# BPF.net
KiCad netlist of a schematic drawn in Altium Designer
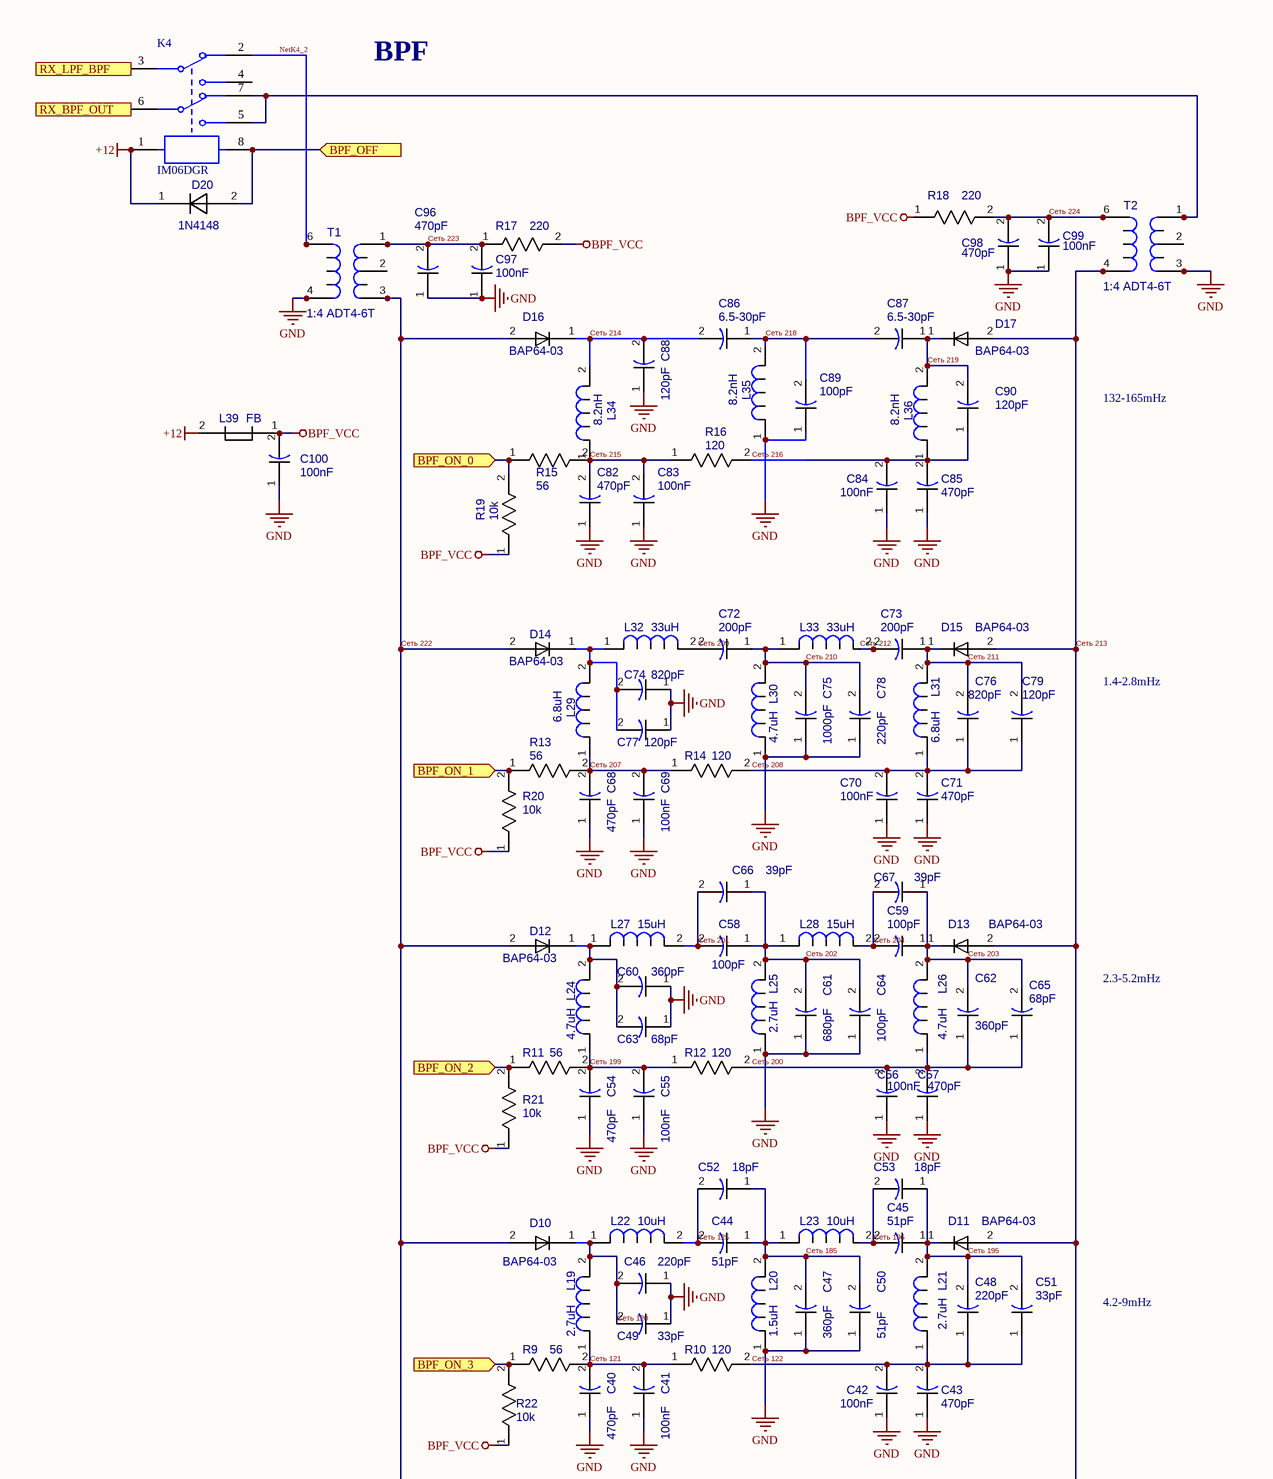
[diagram p0: BPF.SchDoc, top]
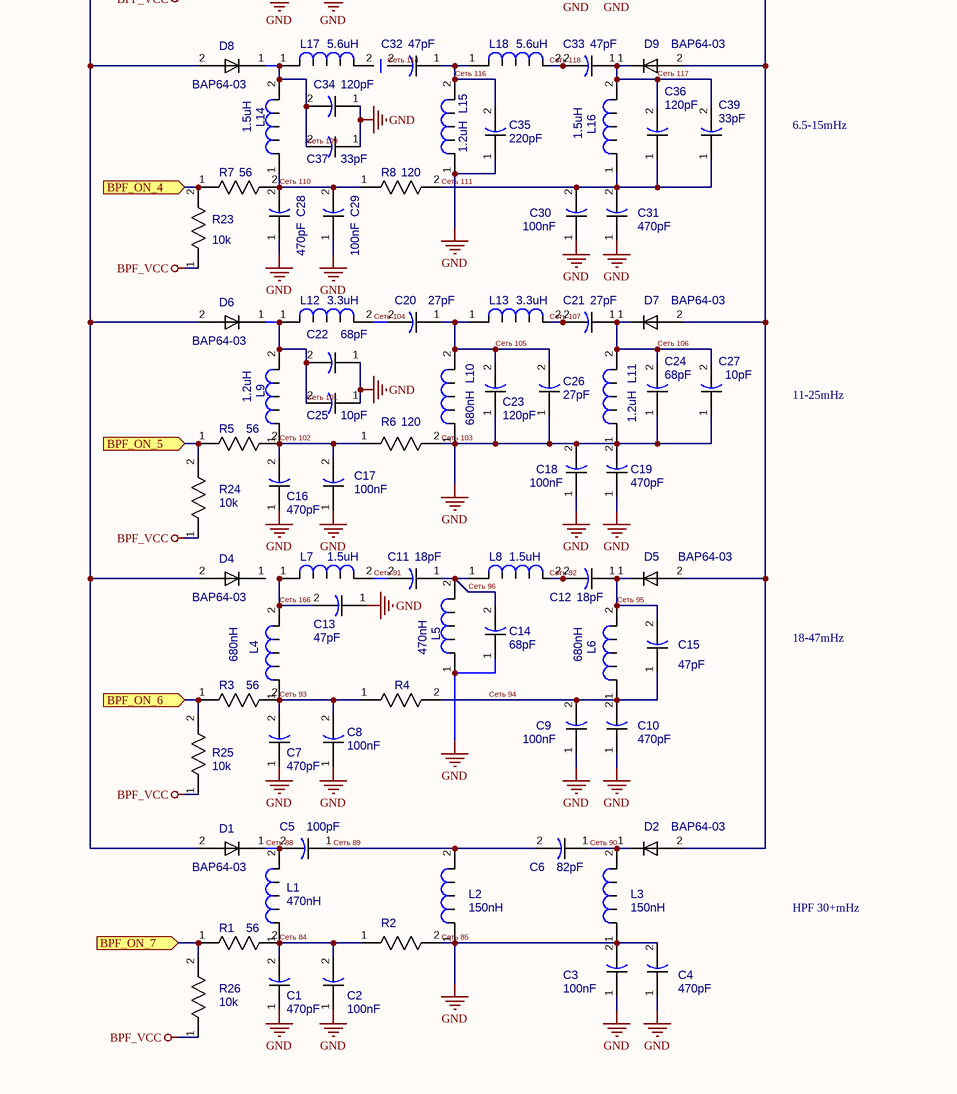
[diagram p1: BPF.SchDoc, bottom]

(export (version "E")
  (design (tool "Eeschema 10.0.6"))
  (components
    (comp (ref "C1")
      (value "470pF")
      (footprint "CAP_0805")
      (description "CAP_0805")
      (libsource (lib "*") (part "CAP_0805"))
    )
    (comp (ref "C2")
      (value "100nF")
      (footprint "CAP_0805")
      (description "CAP_0805")
      (libsource (lib "*") (part "CAP_0805"))
    )
    (comp (ref "C3")
      (value "100nF")
      (footprint "CAP_0805")
      (description "CAP_0805")
      (libsource (lib "*") (part "CAP_0805"))
    )
    (comp (ref "C4")
      (value "470pF")
      (footprint "CAP_0805")
      (description "CAP_0805")
      (libsource (lib "*") (part "CAP_0805"))
    )
    (comp (ref "C5")
      (value "100pF")
      (footprint "CAP_0805")
      (description "CAP_0805")
      (libsource (lib "*") (part "CAP_0805"))
    )
    (comp (ref "C6")
      (value "82pF")
      (footprint "CAP_0805")
      (description "CAP_0805")
      (libsource (lib "*") (part "CAP_0805"))
    )
    (comp (ref "C7")
      (value "470pF")
      (footprint "CAP_0805")
      (description "CAP_0805")
      (libsource (lib "*") (part "CAP_0805"))
    )
    (comp (ref "C8")
      (value "100nF")
      (footprint "CAP_0805")
      (description "CAP_0805")
      (libsource (lib "*") (part "CAP_0805"))
    )
    (comp (ref "C9")
      (value "100nF")
      (footprint "CAP_0805")
      (description "CAP_0805")
      (libsource (lib "*") (part "CAP_0805"))
    )
    (comp (ref "C10")
      (value "470pF")
      (footprint "CAP_0805")
      (description "CAP_0805")
      (libsource (lib "*") (part "CAP_0805"))
    )
    (comp (ref "C11")
      (value "18pF")
      (footprint "CAP_0805")
      (description "CAP_0805")
      (libsource (lib "*") (part "CAP_0805"))
    )
    (comp (ref "C12")
      (value "18pF")
      (footprint "CAP_0805")
      (description "CAP_0805")
      (libsource (lib "*") (part "CAP_0805"))
    )
    (comp (ref "C13")
      (value "47pF")
      (footprint "CAP_0805")
      (description "CAP_0805")
      (libsource (lib "*") (part "CAP_0805"))
    )
    (comp (ref "C14")
      (value "68pF")
      (footprint "CAP_0805")
      (description "CAP_0805")
      (libsource (lib "*") (part "CAP_0805"))
    )
    (comp (ref "C15")
      (value "47pF")
      (footprint "CAP_0805")
      (description "CAP_0805")
      (libsource (lib "*") (part "CAP_0805"))
    )
    (comp (ref "C16")
      (value "470pF")
      (footprint "CAP_0805")
      (description "CAP_0805")
      (libsource (lib "*") (part "CAP_0805"))
    )
    (comp (ref "C17")
      (value "100nF")
      (footprint "CAP_0805")
      (description "CAP_0805")
      (libsource (lib "*") (part "CAP_0805"))
    )
    (comp (ref "C18")
      (value "100nF")
      (footprint "CAP_0805")
      (description "CAP_0805")
      (libsource (lib "*") (part "CAP_0805"))
    )
    (comp (ref "C19")
      (value "470pF")
      (footprint "CAP_0805")
      (description "CAP_0805")
      (libsource (lib "*") (part "CAP_0805"))
    )
    (comp (ref "C20")
      (value "27pF")
      (footprint "CAP_0805")
      (description "CAP_0805")
      (libsource (lib "*") (part "CAP_0805"))
    )
    (comp (ref "C21")
      (value "27pF")
      (footprint "CAP_0805")
      (description "CAP_0805")
      (libsource (lib "*") (part "CAP_0805"))
    )
    (comp (ref "C22")
      (value "68pF")
      (footprint "CAP_0805")
      (description "CAP_0805")
      (libsource (lib "*") (part "CAP_0805"))
    )
    (comp (ref "C23")
      (value "120pF")
      (footprint "CAP_0805")
      (description "CAP_0805")
      (libsource (lib "*") (part "CAP_0805"))
    )
    (comp (ref "C24")
      (value "68pF")
      (footprint "CAP_0805")
      (description "CAP_0805")
      (libsource (lib "*") (part "CAP_0805"))
    )
    (comp (ref "C25")
      (value "10pF")
      (footprint "CAP_0805")
      (description "CAP_0805")
      (libsource (lib "*") (part "CAP_0805"))
    )
    (comp (ref "C26")
      (value "27pF")
      (footprint "CAP_0805")
      (description "CAP_0805")
      (libsource (lib "*") (part "CAP_0805"))
    )
    (comp (ref "C27")
      (value "10pF")
      (footprint "CAP_0805")
      (description "CAP_0805")
      (libsource (lib "*") (part "CAP_0805"))
    )
    (comp (ref "C28")
      (value "470pF")
      (footprint "CAP_0805")
      (description "CAP_0805")
      (libsource (lib "*") (part "CAP_0805"))
    )
    (comp (ref "C29")
      (value "100nF")
      (footprint "CAP_0805")
      (description "CAP_0805")
      (libsource (lib "*") (part "CAP_0805"))
    )
    (comp (ref "C30")
      (value "100nF")
      (footprint "CAP_0805")
      (description "CAP_0805")
      (libsource (lib "*") (part "CAP_0805"))
    )
    (comp (ref "C31")
      (value "470pF")
      (footprint "CAP_0805")
      (description "CAP_0805")
      (libsource (lib "*") (part "CAP_0805"))
    )
    (comp (ref "C32")
      (value "47pF")
      (footprint "CAP_0805")
      (description "CAP_0805")
      (libsource (lib "*") (part "CAP_0805"))
    )
    (comp (ref "C33")
      (value "47pF")
      (footprint "CAP_0805")
      (description "CAP_0805")
      (libsource (lib "*") (part "CAP_0805"))
    )
    (comp (ref "C34")
      (value "120pF")
      (footprint "CAP_0805")
      (description "CAP_0805")
      (libsource (lib "*") (part "CAP_0805"))
    )
    (comp (ref "C35")
      (value "220pF")
      (footprint "CAP_0805")
      (description "CAP_0805")
      (libsource (lib "*") (part "CAP_0805"))
    )
    (comp (ref "C36")
      (value "120pF")
      (footprint "CAP_0805")
      (description "CAP_0805")
      (libsource (lib "*") (part "CAP_0805"))
    )
    (comp (ref "C37")
      (value "33pF")
      (footprint "CAP_0805")
      (description "CAP_0805")
      (libsource (lib "*") (part "CAP_0805"))
    )
    (comp (ref "C39")
      (value "33pF")
      (footprint "CAP_0805")
      (description "CAP_0805")
      (libsource (lib "*") (part "CAP_0805"))
    )
    (comp (ref "C40")
      (value "470pF")
      (footprint "CAP_0805")
      (description "CAP_0805")
      (libsource (lib "*") (part "CAP_0805"))
    )
    (comp (ref "C41")
      (value "100nF")
      (footprint "CAP_0805")
      (description "CAP_0805")
      (libsource (lib "*") (part "CAP_0805"))
    )
    (comp (ref "C42")
      (value "100nF")
      (footprint "CAP_0805")
      (description "CAP_0805")
      (libsource (lib "*") (part "CAP_0805"))
    )
    (comp (ref "C43")
      (value "470pF")
      (footprint "CAP_0805")
      (description "CAP_0805")
      (libsource (lib "*") (part "CAP_0805"))
    )
    (comp (ref "C44")
      (value "51pF")
      (footprint "CAP_0805")
      (description "CAP_0805")
      (libsource (lib "*") (part "CAP_0805"))
    )
    (comp (ref "C45")
      (value "51pF")
      (footprint "CAP_0805")
      (description "CAP_0805")
      (libsource (lib "*") (part "CAP_0805"))
    )
    (comp (ref "C46")
      (value "220pF")
      (footprint "CAP_0805")
      (description "CAP_0805")
      (libsource (lib "*") (part "CAP_0805"))
    )
    (comp (ref "C47")
      (value "360pF")
      (footprint "CAP_0805")
      (description "CAP_0805")
      (libsource (lib "*") (part "CAP_0805"))
    )
    (comp (ref "C48")
      (value "220pF")
      (footprint "CAP_0805")
      (description "CAP_0805")
      (libsource (lib "*") (part "CAP_0805"))
    )
    (comp (ref "C49")
      (value "33pF")
      (footprint "CAP_0805")
      (description "CAP_0805")
      (libsource (lib "*") (part "CAP_0805"))
    )
    (comp (ref "C50")
      (value "51pF")
      (footprint "CAP_0805")
      (description "CAP_0805")
      (libsource (lib "*") (part "CAP_0805"))
    )
    (comp (ref "C51")
      (value "33pF")
      (footprint "CAP_0805")
      (description "CAP_0805")
      (libsource (lib "*") (part "CAP_0805"))
    )
    (comp (ref "C52")
      (value "18pF")
      (footprint "CAP_0805")
      (description "CAP_0805")
      (libsource (lib "*") (part "CAP_0805"))
    )
    (comp (ref "C53")
      (value "18pF")
      (footprint "CAP_0805")
      (description "CAP_0805")
      (libsource (lib "*") (part "CAP_0805"))
    )
    (comp (ref "C54")
      (value "470pF")
      (footprint "CAP_0805")
      (description "CAP_0805")
      (libsource (lib "*") (part "CAP_0805"))
    )
    (comp (ref "C55")
      (value "100nF")
      (footprint "CAP_0805")
      (description "CAP_0805")
      (libsource (lib "*") (part "CAP_0805"))
    )
    (comp (ref "C56")
      (value "100nF")
      (footprint "CAP_0805")
      (description "CAP_0805")
      (libsource (lib "*") (part "CAP_0805"))
    )
    (comp (ref "C57")
      (value "470pF")
      (footprint "CAP_0805")
      (description "CAP_0805")
      (libsource (lib "*") (part "CAP_0805"))
    )
    (comp (ref "C58")
      (value "100pF")
      (footprint "CAP_0805")
      (description "CAP_0805")
      (libsource (lib "*") (part "CAP_0805"))
    )
    (comp (ref "C59")
      (value "100pF")
      (footprint "CAP_0805")
      (description "CAP_0805")
      (libsource (lib "*") (part "CAP_0805"))
    )
    (comp (ref "C60")
      (value "360pF")
      (footprint "CAP_0805")
      (description "CAP_0805")
      (libsource (lib "*") (part "CAP_0805"))
    )
    (comp (ref "C61")
      (value "680pF")
      (footprint "CAP_0805")
      (description "CAP_0805")
      (libsource (lib "*") (part "CAP_0805"))
    )
    (comp (ref "C62")
      (value "360pF")
      (footprint "CAP_0805")
      (description "CAP_0805")
      (libsource (lib "*") (part "CAP_0805"))
    )
    (comp (ref "C63")
      (value "68pF")
      (footprint "CAP_0805")
      (description "CAP_0805")
      (libsource (lib "*") (part "CAP_0805"))
    )
    (comp (ref "C64")
      (value "100pF")
      (footprint "CAP_0805")
      (description "CAP_0805")
      (libsource (lib "*") (part "CAP_0805"))
    )
    (comp (ref "C65")
      (value "68pF")
      (footprint "CAP_0805")
      (description "CAP_0805")
      (libsource (lib "*") (part "CAP_0805"))
    )
    (comp (ref "C66")
      (value "39pF")
      (footprint "CAP_0805")
      (description "CAP_0805")
      (libsource (lib "*") (part "CAP_0805"))
    )
    (comp (ref "C67")
      (value "39pF")
      (footprint "CAP_0805")
      (description "CAP_0805")
      (libsource (lib "*") (part "CAP_0805"))
    )
    (comp (ref "C68")
      (value "470pF")
      (footprint "CAP_0805")
      (description "CAP_0805")
      (libsource (lib "*") (part "CAP_0805"))
    )
    (comp (ref "C69")
      (value "100nF")
      (footprint "CAP_0805")
      (description "CAP_0805")
      (libsource (lib "*") (part "CAP_0805"))
    )
    (comp (ref "C70")
      (value "100nF")
      (footprint "CAP_0805")
      (description "CAP_0805")
      (libsource (lib "*") (part "CAP_0805"))
    )
    (comp (ref "C71")
      (value "470pF")
      (footprint "CAP_0805")
      (description "CAP_0805")
      (libsource (lib "*") (part "CAP_0805"))
    )
    (comp (ref "C72")
      (value "200pF")
      (footprint "CAP_0805")
      (description "CAP_0805")
      (libsource (lib "*") (part "CAP_0805"))
    )
    (comp (ref "C73")
      (value "200pF")
      (footprint "CAP_0805")
      (description "CAP_0805")
      (libsource (lib "*") (part "CAP_0805"))
    )
    (comp (ref "C74")
      (value "820pF")
      (footprint "CAP_0805")
      (description "CAP_0805")
      (libsource (lib "*") (part "CAP_0805"))
    )
    (comp (ref "C75")
      (value "1000pF")
      (footprint "CAP_0805")
      (description "CAP_0805")
      (libsource (lib "*") (part "CAP_0805"))
    )
    (comp (ref "C76")
      (value "820pF")
      (footprint "CAP_0805")
      (description "CAP_0805")
      (libsource (lib "*") (part "CAP_0805"))
    )
    (comp (ref "C77")
      (value "120pF")
      (footprint "CAP_0805")
      (description "CAP_0805")
      (libsource (lib "*") (part "CAP_0805"))
    )
    (comp (ref "C78")
      (value "220pF")
      (footprint "CAP_0805")
      (description "CAP_0805")
      (libsource (lib "*") (part "CAP_0805"))
    )
    (comp (ref "C79")
      (value "120pF")
      (footprint "CAP_0805")
      (description "CAP_0805")
      (libsource (lib "*") (part "CAP_0805"))
    )
    (comp (ref "C82")
      (value "470pF")
      (footprint "CAP_0805")
      (description "CAP_0805")
      (libsource (lib "*") (part "CAP_0805"))
    )
    (comp (ref "C83")
      (value "100nF")
      (footprint "CAP_0805")
      (description "CAP_0805")
      (libsource (lib "*") (part "CAP_0805"))
    )
    (comp (ref "C84")
      (value "100nF")
      (footprint "CAP_0805")
      (description "CAP_0805")
      (libsource (lib "*") (part "CAP_0805"))
    )
    (comp (ref "C85")
      (value "470pF")
      (footprint "CAP_0805")
      (description "CAP_0805")
      (libsource (lib "*") (part "CAP_0805"))
    )
    (comp (ref "C86")
      (value "6.5-30pF")
      (footprint "CAP_1206")
      (description "CAP_0805")
      (libsource (lib "*") (part "CAP_0805"))
    )
    (comp (ref "C87")
      (value "6.5-30pF")
      (footprint "CAP_1206")
      (description "CAP_0805")
      (libsource (lib "*") (part "CAP_0805"))
    )
    (comp (ref "C88")
      (value "120pF")
      (footprint "CAP_0805")
      (description "CAP_0805")
      (libsource (lib "*") (part "CAP_0805"))
    )
    (comp (ref "C89")
      (value "100pF")
      (footprint "CAP_0805")
      (description "CAP_0805")
      (libsource (lib "*") (part "CAP_0805"))
    )
    (comp (ref "C90")
      (value "120pF")
      (footprint "CAP_0805")
      (description "CAP_0805")
      (libsource (lib "*") (part "CAP_0805"))
    )
    (comp (ref "C96")
      (value "470pF")
      (footprint "CAP_0805")
      (description "CAP_0805")
      (libsource (lib "*") (part "CAP_0805"))
    )
    (comp (ref "C97")
      (value "100nF")
      (footprint "CAP_0805")
      (description "CAP_0805")
      (libsource (lib "*") (part "CAP_0805"))
    )
    (comp (ref "C98")
      (value "470pF")
      (footprint "CAP_0805")
      (description "CAP_0805")
      (libsource (lib "*") (part "CAP_0805"))
    )
    (comp (ref "C99")
      (value "100nF")
      (footprint "CAP_0805")
      (description "CAP_0805")
      (libsource (lib "*") (part "CAP_0805"))
    )
    (comp (ref "C100")
      (value "100nF")
      (footprint "CAP_0805")
      (description "CAP_0805")
      (libsource (lib "*") (part "CAP_0805"))
    )
    (comp (ref "D1") (value "BAP64-03") (footprint "SOD-323") (libsource (lib "*") (part "BAP64-03")))
    (comp (ref "D2") (value "BAP64-03") (footprint "SOD-323") (libsource (lib "*") (part "BAP64-03")))
    (comp (ref "D4") (value "BAP64-03") (footprint "SOD-323") (libsource (lib "*") (part "BAP64-03")))
    (comp (ref "D5") (value "BAP64-03") (footprint "SOD-323") (libsource (lib "*") (part "BAP64-03")))
    (comp (ref "D6") (value "BAP64-03") (footprint "SOD-323") (libsource (lib "*") (part "BAP64-03")))
    (comp (ref "D7") (value "BAP64-03") (footprint "SOD-323") (libsource (lib "*") (part "BAP64-03")))
    (comp (ref "D8") (value "BAP64-03") (footprint "SOD-323") (libsource (lib "*") (part "BAP64-03")))
    (comp (ref "D9") (value "BAP64-03") (footprint "SOD-323") (libsource (lib "*") (part "BAP64-03")))
    (comp (ref "D10") (value "BAP64-03") (footprint "SOD-323") (libsource (lib "*") (part "BAP64-03")))
    (comp (ref "D11") (value "BAP64-03") (footprint "SOD-323") (libsource (lib "*") (part "BAP64-03")))
    (comp (ref "D12") (value "BAP64-03") (footprint "SOD-323") (libsource (lib "*") (part "BAP64-03")))
    (comp (ref "D13") (value "BAP64-03") (footprint "SOD-323") (libsource (lib "*") (part "BAP64-03")))
    (comp (ref "D14") (value "BAP64-03") (footprint "SOD-323") (libsource (lib "*") (part "BAP64-03")))
    (comp (ref "D15") (value "BAP64-03") (footprint "SOD-323") (libsource (lib "*") (part "BAP64-03")))
    (comp (ref "D16") (value "BAP64-03") (footprint "SOD-323") (libsource (lib "*") (part "BAP64-03")))
    (comp (ref "D17") (value "BAP64-03") (footprint "SOD-323") (libsource (lib "*") (part "BAP64-03")))
    (comp (ref "D20") (value "1N4148") (footprint "1N4148") (libsource (lib "*") (part "1N4148")))
    (comp (ref "K4")
      (value "IM06DGR")
      (footprint "TECO-SMT-8_V")
      (description "Signal Relay, 5 A, 12 VDC, -40 to 85 degC, 8-Pin SMD, RoHS, Tape and Reel")
      (fields
        (field (name "MANUFACTURER") "TE Connectivity")
        (field (name "APPROVAL CATEGORY") "ULRecognised")
        (field (name "APPROVAL BODIES") "EN/IEC")
      )
      (libsource (lib "Altium Content Vault") (part "RELAY-DPDT-8_C"))
    )
    (comp (ref "L1")
      (value "470nH")
      (footprint "IND_0805")
      (description "IND_0805")
      (libsource (lib "*") (part "IND_0805"))
    )
    (comp (ref "L2")
      (value "150nH")
      (footprint "IND_0805")
      (description "IND_0805")
      (libsource (lib "*") (part "IND_0805"))
    )
    (comp (ref "L3")
      (value "150nH")
      (footprint "IND_0805")
      (description "IND_0805")
      (libsource (lib "*") (part "IND_0805"))
    )
    (comp (ref "L4")
      (value "680nH")
      (footprint "IND_0805")
      (description "IND_0805")
      (libsource (lib "*") (part "IND_0805"))
    )
    (comp (ref "L5")
      (value "470nH")
      (footprint "IND_0805")
      (description "IND_0805")
      (libsource (lib "*") (part "IND_0805"))
    )
    (comp (ref "L6")
      (value "680nH")
      (footprint "IND_0805")
      (description "IND_0805")
      (libsource (lib "*") (part "IND_0805"))
    )
    (comp (ref "L7")
      (value "1.5uH")
      (footprint "IND_0805")
      (description "IND_0805")
      (libsource (lib "*") (part "IND_0805"))
    )
    (comp (ref "L8")
      (value "1.5uH")
      (footprint "IND_0805")
      (description "IND_0805")
      (libsource (lib "*") (part "IND_0805"))
    )
    (comp (ref "L9")
      (value "1.2uH")
      (footprint "IND_0805")
      (description "IND_0805")
      (libsource (lib "*") (part "IND_0805"))
    )
    (comp (ref "L10")
      (value "680nH")
      (footprint "IND_0805")
      (description "IND_0805")
      (libsource (lib "*") (part "IND_0805"))
    )
    (comp (ref "L11")
      (value "1.2uH")
      (footprint "IND_0805")
      (description "IND_0805")
      (libsource (lib "*") (part "IND_0805"))
    )
    (comp (ref "L12")
      (value "3.3uH")
      (footprint "IND_0805")
      (description "IND_0805")
      (libsource (lib "*") (part "IND_0805"))
    )
    (comp (ref "L13")
      (value "3.3uH")
      (footprint "IND_0805")
      (description "IND_0805")
      (libsource (lib "*") (part "IND_0805"))
    )
    (comp (ref "L14")
      (value "1.5uH")
      (footprint "IND_0805")
      (description "IND_0805")
      (libsource (lib "*") (part "IND_0805"))
    )
    (comp (ref "L15")
      (value "1.2uH")
      (footprint "IND_0805")
      (description "IND_0805")
      (libsource (lib "*") (part "IND_0805"))
    )
    (comp (ref "L16")
      (value "1.5uH")
      (footprint "IND_0805")
      (description "IND_0805")
      (libsource (lib "*") (part "IND_0805"))
    )
    (comp (ref "L17")
      (value "5.6uH")
      (footprint "IND_0805")
      (description "IND_0805")
      (libsource (lib "*") (part "IND_0805"))
    )
    (comp (ref "L18")
      (value "5.6uH")
      (footprint "IND_0805")
      (description "IND_0805")
      (libsource (lib "*") (part "IND_0805"))
    )
    (comp (ref "L19")
      (value "2.7uH")
      (footprint "IND_0805")
      (description "IND_0805")
      (libsource (lib "*") (part "IND_0805"))
    )
    (comp (ref "L20")
      (value "1.5uH")
      (footprint "IND_0805")
      (description "IND_0805")
      (libsource (lib "*") (part "IND_0805"))
    )
    (comp (ref "L21")
      (value "2.7uH")
      (footprint "IND_0805")
      (description "IND_0805")
      (libsource (lib "*") (part "IND_0805"))
    )
    (comp (ref "L22")
      (value "10uH")
      (footprint "IND_0805")
      (description "IND_0805")
      (libsource (lib "*") (part "IND_0805"))
    )
    (comp (ref "L23")
      (value "10uH")
      (footprint "IND_0805")
      (description "IND_0805")
      (libsource (lib "*") (part "IND_0805"))
    )
    (comp (ref "L24")
      (value "4.7uH")
      (footprint "IND_0805")
      (description "IND_0805")
      (libsource (lib "*") (part "IND_0805"))
    )
    (comp (ref "L25")
      (value "2.7uH")
      (footprint "IND_0805")
      (description "IND_0805")
      (libsource (lib "*") (part "IND_0805"))
    )
    (comp (ref "L26")
      (value "4.7uH")
      (footprint "IND_0805")
      (description "IND_0805")
      (libsource (lib "*") (part "IND_0805"))
    )
    (comp (ref "L27")
      (value "15uH")
      (footprint "IND_0805")
      (description "IND_0805")
      (libsource (lib "*") (part "IND_0805"))
    )
    (comp (ref "L28")
      (value "15uH")
      (footprint "IND_0805")
      (description "IND_0805")
      (libsource (lib "*") (part "IND_0805"))
    )
    (comp (ref "L29")
      (value "6.8uH")
      (footprint "IND_0805")
      (description "IND_0805")
      (libsource (lib "*") (part "IND_0805"))
    )
    (comp (ref "L30")
      (value "4.7uH")
      (footprint "IND_0805")
      (description "IND_0805")
      (libsource (lib "*") (part "IND_0805"))
    )
    (comp (ref "L31")
      (value "6.8uH")
      (footprint "IND_0805")
      (description "IND_0805")
      (libsource (lib "*") (part "IND_0805"))
    )
    (comp (ref "L32")
      (value "33uH")
      (footprint "IND_0805")
      (description "IND_0805")
      (libsource (lib "*") (part "IND_0805"))
    )
    (comp (ref "L33")
      (value "33uH")
      (footprint "IND_0805")
      (description "IND_0805")
      (libsource (lib "*") (part "IND_0805"))
    )
    (comp (ref "L34")
      (value "8.2nH")
      (footprint "IND_0805")
      (description "IND_0805")
      (libsource (lib "*") (part "IND_0805"))
    )
    (comp (ref "L35")
      (value "8.2nH")
      (footprint "IND_0805")
      (description "IND_0805")
      (libsource (lib "*") (part "IND_0805"))
    )
    (comp (ref "L36")
      (value "8.2nH")
      (footprint "IND_0805")
      (description "IND_0805")
      (libsource (lib "*") (part "IND_0805"))
    )
    (comp (ref "L39")
      (value "FB")
      (footprint "IND_FERRITE_BEAD")
      (description "Ferrite bead on conductor")
      (fields (field (name "Comment") "IND_FERRITE_BEAD"))
      (libsource (lib "*") (part "IND_FERRITE_BEAD"))
    )
    (comp (ref "R1")
      (value "56")
      (footprint "RES_0805")
      (description "RES_0805")
      (libsource (lib "*") (part "RES_0805"))
    )
    (comp (ref "R2") (value "RES_0805") (footprint "RES_0805") (libsource (lib "*") (part "RES_0805")))
    (comp (ref "R3")
      (value "56")
      (footprint "RES_0805")
      (description "RES_0805")
      (libsource (lib "*") (part "RES_0805"))
    )
    (comp (ref "R4") (value "RES_0805") (footprint "RES_0805") (libsource (lib "*") (part "RES_0805")))
    (comp (ref "R5")
      (value "56")
      (footprint "RES_0805")
      (description "RES_0805")
      (libsource (lib "*") (part "RES_0805"))
    )
    (comp (ref "R6")
      (value "120")
      (footprint "RES_0805")
      (description "RES_0805")
      (libsource (lib "*") (part "RES_0805"))
    )
    (comp (ref "R7")
      (value "56")
      (footprint "RES_0805")
      (description "RES_0805")
      (libsource (lib "*") (part "RES_0805"))
    )
    (comp (ref "R8")
      (value "120")
      (footprint "RES_0805")
      (description "RES_0805")
      (libsource (lib "*") (part "RES_0805"))
    )
    (comp (ref "R9")
      (value "56")
      (footprint "RES_0805")
      (description "RES_0805")
      (libsource (lib "*") (part "RES_0805"))
    )
    (comp (ref "R10")
      (value "120")
      (footprint "RES_0805")
      (description "RES_0805")
      (libsource (lib "*") (part "RES_0805"))
    )
    (comp (ref "R11")
      (value "56")
      (footprint "RES_0805")
      (description "RES_0805")
      (libsource (lib "*") (part "RES_0805"))
    )
    (comp (ref "R12")
      (value "120")
      (footprint "RES_0805")
      (description "RES_0805")
      (libsource (lib "*") (part "RES_0805"))
    )
    (comp (ref "R13")
      (value "56")
      (footprint "RES_0805")
      (description "RES_0805")
      (libsource (lib "*") (part "RES_0805"))
    )
    (comp (ref "R14")
      (value "120")
      (footprint "RES_0805")
      (description "RES_0805")
      (libsource (lib "*") (part "RES_0805"))
    )
    (comp (ref "R15")
      (value "56")
      (footprint "RES_0805")
      (description "RES_0805")
      (libsource (lib "*") (part "RES_0805"))
    )
    (comp (ref "R16")
      (value "120")
      (footprint "RES_0805")
      (description "RES_0805")
      (libsource (lib "*") (part "RES_0805"))
    )
    (comp (ref "R17")
      (value "220")
      (footprint "RES_0805")
      (description "RES_0805")
      (libsource (lib "*") (part "RES_0805"))
    )
    (comp (ref "R18")
      (value "220")
      (footprint "RES_0805")
      (description "RES_0805")
      (libsource (lib "*") (part "RES_0805"))
    )
    (comp (ref "R19")
      (value "10k")
      (footprint "RES_0805")
      (description "RES_0805")
      (libsource (lib "*") (part "RES_0805"))
    )
    (comp (ref "R20")
      (value "10k")
      (footprint "RES_0805")
      (description "RES_0805")
      (libsource (lib "*") (part "RES_0805"))
    )
    (comp (ref "R21")
      (value "10k")
      (footprint "RES_0805")
      (description "RES_0805")
      (libsource (lib "*") (part "RES_0805"))
    )
    (comp (ref "R22")
      (value "10k")
      (footprint "RES_0805")
      (description "RES_0805")
      (libsource (lib "*") (part "RES_0805"))
    )
    (comp (ref "R23")
      (value "10k")
      (footprint "RES_0805")
      (description "RES_0805")
      (libsource (lib "*") (part "RES_0805"))
    )
    (comp (ref "R24")
      (value "10k")
      (footprint "RES_0805")
      (description "RES_0805")
      (libsource (lib "*") (part "RES_0805"))
    )
    (comp (ref "R25")
      (value "10k")
      (footprint "RES_0805")
      (description "RES_0805")
      (libsource (lib "*") (part "RES_0805"))
    )
    (comp (ref "R26")
      (value "10k")
      (footprint "RES_0805")
      (description "RES_0805")
      (libsource (lib "*") (part "RES_0805"))
    )
    (comp (ref "T1")
      (value "1:4 ADT4-6T")
      (footprint "TRANSF_ACORE2")
      (description "Transformer")
      (fields (field (name "Comment") "TRANSF_ACORE2"))
      (libsource (lib "RF-UNIT_1") (part "TRANSF_ACORE2"))
    )
    (comp (ref "T2")
      (value "1:4 ADT4-6T")
      (footprint "TRANSF_ACORE2")
      (description "Transformer")
      (fields (field (name "Comment") "TRANSF_ACORE2"))
      (libsource (lib "RF-UNIT_1") (part "TRANSF_ACORE2"))
    )
  )
  (nets
    (net (code "1") (name "+12") (class "Default")
      (node (ref "D20") (pin "1") (pinfunction "K_1") (pintype "passive"))
      (node (ref "K4") (pin "1") (pinfunction "1_1") (pintype "passive"))
      (node (ref "L39") (pin "2") (pinfunction "2_2") (pintype "passive"))
    )
    (net (code "2") (name "/BPF_OFF") (class "Default")
      (node (ref "D20") (pin "2") (pinfunction "A_2") (pintype "passive"))
      (node (ref "K4") (pin "8") (pinfunction "8_8") (pintype "passive"))
    )
    (net (code "3") (name "/BPF_ON_0") (class "Default")
      (node (ref "R15") (pin "1") (pinfunction "1_1") (pintype "passive"))
      (node (ref "R19") (pin "2") (pinfunction "2_2") (pintype "passive"))
    )
    (net (code "4") (name "/BPF_ON_1") (class "Default")
      (node (ref "R13") (pin "1") (pinfunction "1_1") (pintype "passive"))
      (node (ref "R20") (pin "2") (pinfunction "2_2") (pintype "passive"))
    )
    (net (code "5") (name "/BPF_ON_2") (class "Default")
      (node (ref "R11") (pin "1") (pinfunction "1_1") (pintype "passive"))
      (node (ref "R21") (pin "2") (pinfunction "2_2") (pintype "passive"))
    )
    (net (code "6") (name "/BPF_ON_3") (class "Default")
      (node (ref "R22") (pin "2") (pinfunction "2_2") (pintype "passive"))
      (node (ref "R9") (pin "1") (pinfunction "1_1") (pintype "passive"))
    )
    (net (code "7") (name "/BPF_ON_4") (class "Default")
      (node (ref "R23") (pin "2") (pinfunction "2_2") (pintype "passive"))
      (node (ref "R7") (pin "1") (pinfunction "1_1") (pintype "passive"))
    )
    (net (code "8") (name "/BPF_ON_5") (class "Default")
      (node (ref "R24") (pin "2") (pinfunction "2_2") (pintype "passive"))
      (node (ref "R5") (pin "1") (pinfunction "1_1") (pintype "passive"))
    )
    (net (code "9") (name "/BPF_ON_6") (class "Default")
      (node (ref "R25") (pin "2") (pinfunction "2_2") (pintype "passive"))
      (node (ref "R3") (pin "1") (pinfunction "1_1") (pintype "passive"))
    )
    (net (code "10") (name "/BPF_ON_7") (class "Default")
      (node (ref "R1") (pin "1") (pinfunction "1_1") (pintype "passive"))
      (node (ref "R26") (pin "2") (pinfunction "2_2") (pintype "passive"))
    )
    (net (code "11") (name "/NetK4_2") (class "Default")
      (node (ref "K4") (pin "2") (pinfunction "2_2") (pintype "passive"))
      (node (ref "T1") (pin "10") (pinfunction "0_10") (pintype "passive"))
      (node (ref "T1") (pin "6") (pinfunction "P2_6") (pintype "passive"))
    )
    (net (code "12") (name "/RX_BPF_OUT") (class "Default")
      (node (ref "K4") (pin "6") (pinfunction "6_6") (pintype "passive"))
    )
    (net (code "13") (name "/RX_LPF_BPF") (class "Default")
      (node (ref "K4") (pin "3") (pinfunction "3_3") (pintype "passive"))
    )
    (net (code "14") (name "/Сеть 84") (class "Default")
      (node (ref "C1") (pin "2") (pinfunction "2_2") (pintype "passive"))
      (node (ref "C2") (pin "2") (pinfunction "2_2") (pintype "passive"))
      (node (ref "L1") (pin "1") (pinfunction "1_1") (pintype "passive"))
      (node (ref "R1") (pin "2") (pinfunction "2_2") (pintype "passive"))
      (node (ref "R2") (pin "1") (pinfunction "1_1") (pintype "passive"))
    )
    (net (code "15") (name "/Сеть 88") (class "Default")
      (node (ref "C5") (pin "2") (pinfunction "2_2") (pintype "passive"))
      (node (ref "D1") (pin "1") (pinfunction "(C)_1") (pintype "passive"))
      (node (ref "L1") (pin "2") (pinfunction "2_2") (pintype "passive"))
    )
    (net (code "16") (name "/Сеть 89") (class "Default")
      (node (ref "C5") (pin "1") (pinfunction "1_1") (pintype "passive"))
      (node (ref "C6") (pin "2") (pinfunction "2_2") (pintype "passive"))
      (node (ref "L2") (pin "2") (pinfunction "2_2") (pintype "passive"))
    )
    (net (code "17") (name "/Сеть 90") (class "Default")
      (node (ref "C6") (pin "1") (pinfunction "1_1") (pintype "passive"))
      (node (ref "D2") (pin "1") (pinfunction "(C)_1") (pintype "passive"))
      (node (ref "L3") (pin "2") (pinfunction "2_2") (pintype "passive"))
    )
    (net (code "18") (name "/Сеть 91") (class "Default")
      (node (ref "C11") (pin "2") (pinfunction "2_2") (pintype "passive"))
      (node (ref "L7") (pin "2") (pinfunction "2_2") (pintype "passive"))
    )
    (net (code "19") (name "/Сеть 92") (class "Default")
      (node (ref "C12") (pin "2") (pinfunction "2_2") (pintype "passive"))
      (node (ref "L8") (pin "2") (pinfunction "2_2") (pintype "passive"))
    )
    (net (code "20") (name "/Сеть 93") (class "Default")
      (node (ref "C7") (pin "2") (pinfunction "2_2") (pintype "passive"))
      (node (ref "C8") (pin "2") (pinfunction "2_2") (pintype "passive"))
      (node (ref "L4") (pin "1") (pinfunction "1_1") (pintype "passive"))
      (node (ref "R3") (pin "2") (pinfunction "2_2") (pintype "passive"))
      (node (ref "R4") (pin "1") (pinfunction "1_1") (pintype "passive"))
    )
    (net (code "21") (name "/Сеть 94") (class "Default")
      (node (ref "C10") (pin "2") (pinfunction "2_2") (pintype "passive"))
      (node (ref "C15") (pin "1") (pinfunction "1_1") (pintype "passive"))
      (node (ref "C9") (pin "2") (pinfunction "2_2") (pintype "passive"))
      (node (ref "L6") (pin "1") (pinfunction "1_1") (pintype "passive"))
      (node (ref "R4") (pin "2") (pinfunction "2_2") (pintype "passive"))
    )
    (net (code "22") (name "/Сеть 95") (class "Default")
      (node (ref "C12") (pin "1") (pinfunction "1_1") (pintype "passive"))
      (node (ref "C15") (pin "2") (pinfunction "2_2") (pintype "passive"))
      (node (ref "D5") (pin "1") (pinfunction "(C)_1") (pintype "passive"))
      (node (ref "L6") (pin "2") (pinfunction "2_2") (pintype "passive"))
    )
    (net (code "23") (name "/Сеть 96") (class "Default")
      (node (ref "C11") (pin "1") (pinfunction "1_1") (pintype "passive"))
      (node (ref "C14") (pin "2") (pinfunction "2_2") (pintype "passive"))
      (node (ref "L5") (pin "2") (pinfunction "2_2") (pintype "passive"))
      (node (ref "L8") (pin "1") (pinfunction "1_1") (pintype "passive"))
    )
    (net (code "24") (name "/Сеть 101") (class "Default")
      (node (ref "C22") (pin "2") (pinfunction "2_2") (pintype "passive"))
      (node (ref "C25") (pin "2") (pinfunction "2_2") (pintype "passive"))
      (node (ref "D6") (pin "1") (pinfunction "(C)_1") (pintype "passive"))
      (node (ref "L12") (pin "1") (pinfunction "1_1") (pintype "passive"))
      (node (ref "L9") (pin "2") (pinfunction "2_2") (pintype "passive"))
    )
    (net (code "25") (name "/Сеть 102") (class "Default")
      (node (ref "C16") (pin "2") (pinfunction "2_2") (pintype "passive"))
      (node (ref "C17") (pin "2") (pinfunction "2_2") (pintype "passive"))
      (node (ref "L9") (pin "1") (pinfunction "1_1") (pintype "passive"))
      (node (ref "R5") (pin "2") (pinfunction "2_2") (pintype "passive"))
      (node (ref "R6") (pin "1") (pinfunction "1_1") (pintype "passive"))
    )
    (net (code "26") (name "/Сеть 104") (class "Default")
      (node (ref "C20") (pin "2") (pinfunction "2_2") (pintype "passive"))
      (node (ref "L12") (pin "2") (pinfunction "2_2") (pintype "passive"))
    )
    (net (code "27") (name "/Сеть 105") (class "Default")
      (node (ref "C20") (pin "1") (pinfunction "1_1") (pintype "passive"))
      (node (ref "C23") (pin "2") (pinfunction "2_2") (pintype "passive"))
      (node (ref "C26") (pin "2") (pinfunction "2_2") (pintype "passive"))
      (node (ref "L10") (pin "2") (pinfunction "2_2") (pintype "passive"))
      (node (ref "L13") (pin "1") (pinfunction "1_1") (pintype "passive"))
    )
    (net (code "28") (name "/Сеть 106") (class "Default")
      (node (ref "C21") (pin "1") (pinfunction "1_1") (pintype "passive"))
      (node (ref "C24") (pin "2") (pinfunction "2_2") (pintype "passive"))
      (node (ref "C27") (pin "2") (pinfunction "2_2") (pintype "passive"))
      (node (ref "D7") (pin "1") (pinfunction "(C)_1") (pintype "passive"))
      (node (ref "L11") (pin "2") (pinfunction "2_2") (pintype "passive"))
    )
    (net (code "29") (name "/Сеть 107") (class "Default")
      (node (ref "C21") (pin "2") (pinfunction "2_2") (pintype "passive"))
      (node (ref "L13") (pin "2") (pinfunction "2_2") (pintype "passive"))
    )
    (net (code "30") (name "/Сеть 109") (class "Default")
      (node (ref "C34") (pin "2") (pinfunction "2_2") (pintype "passive"))
      (node (ref "C37") (pin "2") (pinfunction "2_2") (pintype "passive"))
      (node (ref "D8") (pin "1") (pinfunction "(C)_1") (pintype "passive"))
      (node (ref "L14") (pin "2") (pinfunction "2_2") (pintype "passive"))
      (node (ref "L17") (pin "1") (pinfunction "1_1") (pintype "passive"))
    )
    (net (code "31") (name "/Сеть 110") (class "Default")
      (node (ref "C28") (pin "2") (pinfunction "2_2") (pintype "passive"))
      (node (ref "C29") (pin "2") (pinfunction "2_2") (pintype "passive"))
      (node (ref "L14") (pin "1") (pinfunction "1_1") (pintype "passive"))
      (node (ref "R7") (pin "2") (pinfunction "2_2") (pintype "passive"))
      (node (ref "R8") (pin "1") (pinfunction "1_1") (pintype "passive"))
    )
    (net (code "32") (name "/Сеть 111") (class "Default")
      (node (ref "C30") (pin "2") (pinfunction "2_2") (pintype "passive"))
      (node (ref "C31") (pin "2") (pinfunction "2_2") (pintype "passive"))
      (node (ref "C36") (pin "1") (pinfunction "1_1") (pintype "passive"))
      (node (ref "C39") (pin "1") (pinfunction "1_1") (pintype "passive"))
      (node (ref "L16") (pin "1") (pinfunction "1_1") (pintype "passive"))
      (node (ref "R8") (pin "2") (pinfunction "2_2") (pintype "passive"))
    )
    (net (code "33") (name "/Сеть 114") (class "Default")
      (node (ref "C32") (pin "2") (pinfunction "2_2") (pintype "passive"))
    )
    (net (code "34") (name "/Сеть 116") (class "Default")
      (node (ref "C32") (pin "1") (pinfunction "1_1") (pintype "passive"))
      (node (ref "C35") (pin "2") (pinfunction "2_2") (pintype "passive"))
      (node (ref "L15") (pin "2") (pinfunction "2_2") (pintype "passive"))
      (node (ref "L18") (pin "1") (pinfunction "1_1") (pintype "passive"))
    )
    (net (code "35") (name "/Сеть 117") (class "Default")
      (node (ref "C33") (pin "1") (pinfunction "1_1") (pintype "passive"))
      (node (ref "C36") (pin "2") (pinfunction "2_2") (pintype "passive"))
      (node (ref "C39") (pin "2") (pinfunction "2_2") (pintype "passive"))
      (node (ref "D9") (pin "1") (pinfunction "(C)_1") (pintype "passive"))
      (node (ref "L16") (pin "2") (pinfunction "2_2") (pintype "passive"))
    )
    (net (code "36") (name "/Сеть 118") (class "Default")
      (node (ref "C33") (pin "2") (pinfunction "2_2") (pintype "passive"))
      (node (ref "L18") (pin "2") (pinfunction "2_2") (pintype "passive"))
    )
    (net (code "37") (name "/Сеть 120") (class "Default")
      (node (ref "C46") (pin "2") (pinfunction "2_2") (pintype "passive"))
      (node (ref "C49") (pin "2") (pinfunction "2_2") (pintype "passive"))
      (node (ref "D10") (pin "1") (pinfunction "(C)_1") (pintype "passive"))
      (node (ref "L19") (pin "2") (pinfunction "2_2") (pintype "passive"))
      (node (ref "L22") (pin "1") (pinfunction "1_1") (pintype "passive"))
    )
    (net (code "38") (name "/Сеть 121") (class "Default")
      (node (ref "C40") (pin "2") (pinfunction "2_2") (pintype "passive"))
      (node (ref "C41") (pin "2") (pinfunction "2_2") (pintype "passive"))
      (node (ref "L19") (pin "1") (pinfunction "1_1") (pintype "passive"))
      (node (ref "R10") (pin "1") (pinfunction "1_1") (pintype "passive"))
      (node (ref "R9") (pin "2") (pinfunction "2_2") (pintype "passive"))
    )
    (net (code "39") (name "/Сеть 122") (class "Default")
      (node (ref "C42") (pin "2") (pinfunction "2_2") (pintype "passive"))
      (node (ref "C43") (pin "2") (pinfunction "2_2") (pintype "passive"))
      (node (ref "C48") (pin "1") (pinfunction "1_1") (pintype "passive"))
      (node (ref "C51") (pin "1") (pinfunction "1_1") (pintype "passive"))
      (node (ref "L21") (pin "1") (pinfunction "1_1") (pintype "passive"))
      (node (ref "R10") (pin "2") (pinfunction "2_2") (pintype "passive"))
    )
    (net (code "40") (name "/Сеть 125") (class "Default")
      (node (ref "C44") (pin "2") (pinfunction "2_2") (pintype "passive"))
      (node (ref "C52") (pin "2") (pinfunction "2_2") (pintype "passive"))
      (node (ref "L22") (pin "2") (pinfunction "2_2") (pintype "passive"))
    )
    (net (code "41") (name "/Сеть 166") (class "Default")
      (node (ref "C13") (pin "2") (pinfunction "2_2") (pintype "passive"))
      (node (ref "L4") (pin "2") (pinfunction "2_2") (pintype "passive"))
      (node (ref "L7") (pin "1") (pinfunction "1_1") (pintype "passive"))
    )
    (net (code "42") (name "/Сеть 185") (class "Default")
      (node (ref "C44") (pin "1") (pinfunction "1_1") (pintype "passive"))
      (node (ref "C47") (pin "2") (pinfunction "2_2") (pintype "passive"))
      (node (ref "C50") (pin "2") (pinfunction "2_2") (pintype "passive"))
      (node (ref "C52") (pin "1") (pinfunction "1_1") (pintype "passive"))
      (node (ref "L20") (pin "2") (pinfunction "2_2") (pintype "passive"))
      (node (ref "L23") (pin "1") (pinfunction "1_1") (pintype "passive"))
    )
    (net (code "43") (name "/Сеть 195") (class "Default")
      (node (ref "C45") (pin "1") (pinfunction "1_1") (pintype "passive"))
      (node (ref "C48") (pin "2") (pinfunction "2_2") (pintype "passive"))
      (node (ref "C51") (pin "2") (pinfunction "2_2") (pintype "passive"))
      (node (ref "C53") (pin "1") (pinfunction "1_1") (pintype "passive"))
      (node (ref "D11") (pin "1") (pinfunction "(C)_1") (pintype "passive"))
      (node (ref "L21") (pin "2") (pinfunction "2_2") (pintype "passive"))
    )
    (net (code "44") (name "/Сеть 196") (class "Default")
      (node (ref "C45") (pin "2") (pinfunction "2_2") (pintype "passive"))
      (node (ref "C53") (pin "2") (pinfunction "2_2") (pintype "passive"))
      (node (ref "L23") (pin "2") (pinfunction "2_2") (pintype "passive"))
    )
    (net (code "45") (name "/Сеть 199") (class "Default")
      (node (ref "C54") (pin "2") (pinfunction "2_2") (pintype "passive"))
      (node (ref "C55") (pin "2") (pinfunction "2_2") (pintype "passive"))
      (node (ref "L24") (pin "1") (pinfunction "1_1") (pintype "passive"))
      (node (ref "R11") (pin "2") (pinfunction "2_2") (pintype "passive"))
      (node (ref "R12") (pin "1") (pinfunction "1_1") (pintype "passive"))
    )
    (net (code "46") (name "/Сеть 200") (class "Default")
      (node (ref "C56") (pin "2") (pinfunction "2_2") (pintype "passive"))
      (node (ref "C57") (pin "2") (pinfunction "2_2") (pintype "passive"))
      (node (ref "C62") (pin "1") (pinfunction "1_1") (pintype "passive"))
      (node (ref "C65") (pin "1") (pinfunction "1_1") (pintype "passive"))
      (node (ref "L26") (pin "1") (pinfunction "1_1") (pintype "passive"))
      (node (ref "R12") (pin "2") (pinfunction "2_2") (pintype "passive"))
    )
    (net (code "47") (name "/Сеть 201") (class "Default")
      (node (ref "C58") (pin "2") (pinfunction "2_2") (pintype "passive"))
      (node (ref "C66") (pin "2") (pinfunction "2_2") (pintype "passive"))
      (node (ref "L27") (pin "2") (pinfunction "2_2") (pintype "passive"))
    )
    (net (code "48") (name "/Сеть 202") (class "Default")
      (node (ref "C58") (pin "1") (pinfunction "1_1") (pintype "passive"))
      (node (ref "C61") (pin "2") (pinfunction "2_2") (pintype "passive"))
      (node (ref "C64") (pin "2") (pinfunction "2_2") (pintype "passive"))
      (node (ref "C66") (pin "1") (pinfunction "1_1") (pintype "passive"))
      (node (ref "L25") (pin "2") (pinfunction "2_2") (pintype "passive"))
      (node (ref "L28") (pin "1") (pinfunction "1_1") (pintype "passive"))
    )
    (net (code "49") (name "/Сеть 203") (class "Default")
      (node (ref "C59") (pin "1") (pinfunction "1_1") (pintype "passive"))
      (node (ref "C62") (pin "2") (pinfunction "2_2") (pintype "passive"))
      (node (ref "C65") (pin "2") (pinfunction "2_2") (pintype "passive"))
      (node (ref "C67") (pin "1") (pinfunction "1_1") (pintype "passive"))
      (node (ref "D13") (pin "1") (pinfunction "(C)_1") (pintype "passive"))
      (node (ref "L26") (pin "2") (pinfunction "2_2") (pintype "passive"))
    )
    (net (code "50") (name "/Сеть 204") (class "Default")
      (node (ref "C59") (pin "2") (pinfunction "2_2") (pintype "passive"))
      (node (ref "C67") (pin "2") (pinfunction "2_2") (pintype "passive"))
      (node (ref "L28") (pin "2") (pinfunction "2_2") (pintype "passive"))
    )
    (net (code "51") (name "/Сеть 207") (class "Default")
      (node (ref "C68") (pin "2") (pinfunction "2_2") (pintype "passive"))
      (node (ref "C69") (pin "2") (pinfunction "2_2") (pintype "passive"))
      (node (ref "L29") (pin "1") (pinfunction "1_1") (pintype "passive"))
      (node (ref "R13") (pin "2") (pinfunction "2_2") (pintype "passive"))
      (node (ref "R14") (pin "1") (pinfunction "1_1") (pintype "passive"))
    )
    (net (code "52") (name "/Сеть 208") (class "Default")
      (node (ref "C70") (pin "2") (pinfunction "2_2") (pintype "passive"))
      (node (ref "C71") (pin "2") (pinfunction "2_2") (pintype "passive"))
      (node (ref "C76") (pin "1") (pinfunction "1_1") (pintype "passive"))
      (node (ref "C79") (pin "1") (pinfunction "1_1") (pintype "passive"))
      (node (ref "L31") (pin "1") (pinfunction "1_1") (pintype "passive"))
      (node (ref "R14") (pin "2") (pinfunction "2_2") (pintype "passive"))
    )
    (net (code "53") (name "/Сеть 209") (class "Default")
      (node (ref "C72") (pin "2") (pinfunction "2_2") (pintype "passive"))
      (node (ref "L32") (pin "2") (pinfunction "2_2") (pintype "passive"))
    )
    (net (code "54") (name "/Сеть 210") (class "Default")
      (node (ref "C72") (pin "1") (pinfunction "1_1") (pintype "passive"))
      (node (ref "C75") (pin "2") (pinfunction "2_2") (pintype "passive"))
      (node (ref "C78") (pin "2") (pinfunction "2_2") (pintype "passive"))
      (node (ref "L30") (pin "2") (pinfunction "2_2") (pintype "passive"))
      (node (ref "L33") (pin "1") (pinfunction "1_1") (pintype "passive"))
    )
    (net (code "55") (name "/Сеть 211") (class "Default")
      (node (ref "C73") (pin "1") (pinfunction "1_1") (pintype "passive"))
      (node (ref "C76") (pin "2") (pinfunction "2_2") (pintype "passive"))
      (node (ref "C79") (pin "2") (pinfunction "2_2") (pintype "passive"))
      (node (ref "D15") (pin "1") (pinfunction "(C)_1") (pintype "passive"))
      (node (ref "L31") (pin "2") (pinfunction "2_2") (pintype "passive"))
    )
    (net (code "56") (name "/Сеть 212") (class "Default")
      (node (ref "C73") (pin "2") (pinfunction "2_2") (pintype "passive"))
      (node (ref "L33") (pin "2") (pinfunction "2_2") (pintype "passive"))
    )
    (net (code "57") (name "/Сеть 213") (class "Default")
      (node (ref "D11") (pin "2") (pinfunction "(A)_2") (pintype "passive"))
      (node (ref "D13") (pin "2") (pinfunction "(A)_2") (pintype "passive"))
      (node (ref "D15") (pin "2") (pinfunction "(A)_2") (pintype "passive"))
      (node (ref "D17") (pin "2") (pinfunction "(A)_2") (pintype "passive"))
      (node (ref "D2") (pin "2") (pinfunction "(A)_2") (pintype "passive"))
      (node (ref "D5") (pin "2") (pinfunction "(A)_2") (pintype "passive"))
      (node (ref "D7") (pin "2") (pinfunction "(A)_2") (pintype "passive"))
      (node (ref "D9") (pin "2") (pinfunction "(A)_2") (pintype "passive"))
      (node (ref "T2") (pin "11") (pinfunction "0_11") (pintype "passive"))
      (node (ref "T2") (pin "4") (pinfunction "P1_4") (pintype "passive"))
    )
    (net (code "58") (name "/Сеть 214") (class "Default")
      (node (ref "C86") (pin "2") (pinfunction "2_2") (pintype "passive"))
      (node (ref "C88") (pin "2") (pinfunction "2_2") (pintype "passive"))
      (node (ref "D16") (pin "1") (pinfunction "(C)_1") (pintype "passive"))
      (node (ref "L34") (pin "2") (pinfunction "2_2") (pintype "passive"))
    )
    (net (code "59") (name "/Сеть 215") (class "Default")
      (node (ref "C82") (pin "2") (pinfunction "2_2") (pintype "passive"))
      (node (ref "C83") (pin "2") (pinfunction "2_2") (pintype "passive"))
      (node (ref "L34") (pin "1") (pinfunction "1_1") (pintype "passive"))
      (node (ref "R15") (pin "2") (pinfunction "2_2") (pintype "passive"))
      (node (ref "R16") (pin "1") (pinfunction "1_1") (pintype "passive"))
    )
    (net (code "60") (name "/Сеть 216") (class "Default")
      (node (ref "C84") (pin "2") (pinfunction "2_2") (pintype "passive"))
      (node (ref "C85") (pin "2") (pinfunction "2_2") (pintype "passive"))
      (node (ref "C90") (pin "1") (pinfunction "1_1") (pintype "passive"))
      (node (ref "L36") (pin "1") (pinfunction "1_1") (pintype "passive"))
      (node (ref "R16") (pin "2") (pinfunction "2_2") (pintype "passive"))
    )
    (net (code "61") (name "/Сеть 218") (class "Default")
      (node (ref "C86") (pin "1") (pinfunction "1_1") (pintype "passive"))
      (node (ref "C87") (pin "2") (pinfunction "2_2") (pintype "passive"))
      (node (ref "C89") (pin "2") (pinfunction "2_2") (pintype "passive"))
      (node (ref "L35") (pin "2") (pinfunction "2_2") (pintype "passive"))
    )
    (net (code "62") (name "/Сеть 219") (class "Default")
      (node (ref "C87") (pin "1") (pinfunction "1_1") (pintype "passive"))
      (node (ref "C90") (pin "2") (pinfunction "2_2") (pintype "passive"))
      (node (ref "D17") (pin "1") (pinfunction "(C)_1") (pintype "passive"))
      (node (ref "L36") (pin "2") (pinfunction "2_2") (pintype "passive"))
    )
    (net (code "63") (name "/Сеть 222") (class "Default")
      (node (ref "D1") (pin "2") (pinfunction "(A)_2") (pintype "passive"))
      (node (ref "D10") (pin "2") (pinfunction "(A)_2") (pintype "passive"))
      (node (ref "D12") (pin "2") (pinfunction "(A)_2") (pintype "passive"))
      (node (ref "D14") (pin "2") (pinfunction "(A)_2") (pintype "passive"))
      (node (ref "D16") (pin "2") (pinfunction "(A)_2") (pintype "passive"))
      (node (ref "D4") (pin "2") (pinfunction "(A)_2") (pintype "passive"))
      (node (ref "D6") (pin "2") (pinfunction "(A)_2") (pintype "passive"))
      (node (ref "D8") (pin "2") (pinfunction "(A)_2") (pintype "passive"))
      (node (ref "T1") (pin "3") (pinfunction "S1_3") (pintype "passive"))
      (node (ref "T1") (pin "9") (pinfunction "0_9") (pintype "passive"))
    )
    (net (code "64") (name "/Сеть 223") (class "Default")
      (node (ref "C96") (pin "2") (pinfunction "2_2") (pintype "passive"))
      (node (ref "C97") (pin "2") (pinfunction "2_2") (pintype "passive"))
      (node (ref "R17") (pin "1") (pinfunction "1_1") (pintype "passive"))
      (node (ref "T1") (pin "1") (pinfunction "S3_1") (pintype "passive"))
      (node (ref "T1") (pin "7") (pinfunction "0_7") (pintype "passive"))
    )
    (net (code "65") (name "/Сеть 224") (class "Default")
      (node (ref "C98") (pin "2") (pinfunction "2_2") (pintype "passive"))
      (node (ref "C99") (pin "2") (pinfunction "2_2") (pintype "passive"))
      (node (ref "R18") (pin "2") (pinfunction "2_2") (pintype "passive"))
      (node (ref "T2") (pin "10") (pinfunction "0_10") (pintype "passive"))
      (node (ref "T2") (pin "6") (pinfunction "P2_6") (pintype "passive"))
    )
    (net (code "66") (name "BPF_VCC") (class "Default")
      (node (ref "C100") (pin "2") (pinfunction "2_2") (pintype "passive"))
      (node (ref "L39") (pin "1") (pinfunction "1_1") (pintype "passive"))
      (node (ref "R17") (pin "2") (pinfunction "2_2") (pintype "passive"))
      (node (ref "R18") (pin "1") (pinfunction "1_1") (pintype "passive"))
      (node (ref "R19") (pin "1") (pinfunction "1_1") (pintype "passive"))
      (node (ref "R20") (pin "1") (pinfunction "1_1") (pintype "passive"))
      (node (ref "R21") (pin "1") (pinfunction "1_1") (pintype "passive"))
      (node (ref "R22") (pin "1") (pinfunction "1_1") (pintype "passive"))
      (node (ref "R23") (pin "1") (pinfunction "1_1") (pintype "passive"))
      (node (ref "R24") (pin "1") (pinfunction "1_1") (pintype "passive"))
      (node (ref "R25") (pin "1") (pinfunction "1_1") (pintype "passive"))
      (node (ref "R26") (pin "1") (pinfunction "1_1") (pintype "passive"))
    )
    (net (code "67") (name "GND") (class "Default")
      (node (ref "C1") (pin "1") (pinfunction "1_1") (pintype "passive"))
      (node (ref "C10") (pin "1") (pinfunction "1_1") (pintype "passive"))
      (node (ref "C100") (pin "1") (pinfunction "1_1") (pintype "passive"))
      (node (ref "C13") (pin "1") (pinfunction "1_1") (pintype "passive"))
      (node (ref "C14") (pin "1") (pinfunction "1_1") (pintype "passive"))
      (node (ref "C16") (pin "1") (pinfunction "1_1") (pintype "passive"))
      (node (ref "C17") (pin "1") (pinfunction "1_1") (pintype "passive"))
      (node (ref "C18") (pin "1") (pinfunction "1_1") (pintype "passive"))
      (node (ref "C18") (pin "2") (pinfunction "2_2") (pintype "passive"))
      (node (ref "C19") (pin "1") (pinfunction "1_1") (pintype "passive"))
      (node (ref "C19") (pin "2") (pinfunction "2_2") (pintype "passive"))
      (node (ref "C2") (pin "1") (pinfunction "1_1") (pintype "passive"))
      (node (ref "C22") (pin "1") (pinfunction "1_1") (pintype "passive"))
      (node (ref "C23") (pin "1") (pinfunction "1_1") (pintype "passive"))
      (node (ref "C24") (pin "1") (pinfunction "1_1") (pintype "passive"))
      (node (ref "C25") (pin "1") (pinfunction "1_1") (pintype "passive"))
      (node (ref "C26") (pin "1") (pinfunction "1_1") (pintype "passive"))
      (node (ref "C27") (pin "1") (pinfunction "1_1") (pintype "passive"))
      (node (ref "C28") (pin "1") (pinfunction "1_1") (pintype "passive"))
      (node (ref "C29") (pin "1") (pinfunction "1_1") (pintype "passive"))
      (node (ref "C3") (pin "1") (pinfunction "1_1") (pintype "passive"))
      (node (ref "C3") (pin "2") (pinfunction "2_2") (pintype "passive"))
      (node (ref "C30") (pin "1") (pinfunction "1_1") (pintype "passive"))
      (node (ref "C31") (pin "1") (pinfunction "1_1") (pintype "passive"))
      (node (ref "C34") (pin "1") (pinfunction "1_1") (pintype "passive"))
      (node (ref "C35") (pin "1") (pinfunction "1_1") (pintype "passive"))
      (node (ref "C37") (pin "1") (pinfunction "1_1") (pintype "passive"))
      (node (ref "C4") (pin "1") (pinfunction "1_1") (pintype "passive"))
      (node (ref "C4") (pin "2") (pinfunction "2_2") (pintype "passive"))
      (node (ref "C40") (pin "1") (pinfunction "1_1") (pintype "passive"))
      (node (ref "C41") (pin "1") (pinfunction "1_1") (pintype "passive"))
      (node (ref "C42") (pin "1") (pinfunction "1_1") (pintype "passive"))
      (node (ref "C43") (pin "1") (pinfunction "1_1") (pintype "passive"))
      (node (ref "C46") (pin "1") (pinfunction "1_1") (pintype "passive"))
      (node (ref "C47") (pin "1") (pinfunction "1_1") (pintype "passive"))
      (node (ref "C49") (pin "1") (pinfunction "1_1") (pintype "passive"))
      (node (ref "C50") (pin "1") (pinfunction "1_1") (pintype "passive"))
      (node (ref "C54") (pin "1") (pinfunction "1_1") (pintype "passive"))
      (node (ref "C55") (pin "1") (pinfunction "1_1") (pintype "passive"))
      (node (ref "C56") (pin "1") (pinfunction "1_1") (pintype "passive"))
      (node (ref "C57") (pin "1") (pinfunction "1_1") (pintype "passive"))
      (node (ref "C60") (pin "1") (pinfunction "1_1") (pintype "passive"))
      (node (ref "C61") (pin "1") (pinfunction "1_1") (pintype "passive"))
      (node (ref "C63") (pin "1") (pinfunction "1_1") (pintype "passive"))
      (node (ref "C64") (pin "1") (pinfunction "1_1") (pintype "passive"))
      (node (ref "C68") (pin "1") (pinfunction "1_1") (pintype "passive"))
      (node (ref "C69") (pin "1") (pinfunction "1_1") (pintype "passive"))
      (node (ref "C7") (pin "1") (pinfunction "1_1") (pintype "passive"))
      (node (ref "C70") (pin "1") (pinfunction "1_1") (pintype "passive"))
      (node (ref "C71") (pin "1") (pinfunction "1_1") (pintype "passive"))
      (node (ref "C74") (pin "1") (pinfunction "1_1") (pintype "passive"))
      (node (ref "C75") (pin "1") (pinfunction "1_1") (pintype "passive"))
      (node (ref "C77") (pin "1") (pinfunction "1_1") (pintype "passive"))
      (node (ref "C78") (pin "1") (pinfunction "1_1") (pintype "passive"))
      (node (ref "C8") (pin "1") (pinfunction "1_1") (pintype "passive"))
      (node (ref "C82") (pin "1") (pinfunction "1_1") (pintype "passive"))
      (node (ref "C83") (pin "1") (pinfunction "1_1") (pintype "passive"))
      (node (ref "C84") (pin "1") (pinfunction "1_1") (pintype "passive"))
      (node (ref "C85") (pin "1") (pinfunction "1_1") (pintype "passive"))
      (node (ref "C88") (pin "1") (pinfunction "1_1") (pintype "passive"))
      (node (ref "C89") (pin "1") (pinfunction "1_1") (pintype "passive"))
      (node (ref "C9") (pin "1") (pinfunction "1_1") (pintype "passive"))
      (node (ref "C96") (pin "1") (pinfunction "1_1") (pintype "passive"))
      (node (ref "C97") (pin "1") (pinfunction "1_1") (pintype "passive"))
      (node (ref "C98") (pin "1") (pinfunction "1_1") (pintype "passive"))
      (node (ref "C99") (pin "1") (pinfunction "1_1") (pintype "passive"))
      (node (ref "L10") (pin "1") (pinfunction "1_1") (pintype "passive"))
      (node (ref "L11") (pin "1") (pinfunction "1_1") (pintype "passive"))
      (node (ref "L15") (pin "1") (pinfunction "1_1") (pintype "passive"))
      (node (ref "L2") (pin "1") (pinfunction "1_1") (pintype "passive"))
      (node (ref "L20") (pin "1") (pinfunction "1_1") (pintype "passive"))
      (node (ref "L25") (pin "1") (pinfunction "1_1") (pintype "passive"))
      (node (ref "L3") (pin "1") (pinfunction "1_1") (pintype "passive"))
      (node (ref "L30") (pin "1") (pinfunction "1_1") (pintype "passive"))
      (node (ref "L35") (pin "1") (pinfunction "1_1") (pintype "passive"))
      (node (ref "L5") (pin "1") (pinfunction "1_1") (pintype "passive"))
      (node (ref "R2") (pin "2") (pinfunction "2_2") (pintype "passive"))
      (node (ref "R6") (pin "2") (pinfunction "2_2") (pintype "passive"))
      (node (ref "T1") (pin "11") (pinfunction "0_11") (pintype "passive"))
      (node (ref "T1") (pin "4") (pinfunction "P1_4") (pintype "passive"))
      (node (ref "T2") (pin "3") (pinfunction "S1_3") (pintype "passive"))
      (node (ref "T2") (pin "9") (pinfunction "0_9") (pintype "passive"))
    )
    (net (code "68") (name "Net-(D12-(C))") (class "Default")
      (node (ref "C60") (pin "2") (pinfunction "2_2") (pintype "passive"))
      (node (ref "C63") (pin "2") (pinfunction "2_2") (pintype "passive"))
      (node (ref "D12") (pin "1") (pinfunction "(C)_1") (pintype "passive"))
      (node (ref "L24") (pin "2") (pinfunction "2_2") (pintype "passive"))
      (node (ref "L27") (pin "1") (pinfunction "1_1") (pintype "passive"))
    )
    (net (code "69") (name "Net-(D14-(C))") (class "Default")
      (node (ref "C74") (pin "2") (pinfunction "2_2") (pintype "passive"))
      (node (ref "C77") (pin "2") (pinfunction "2_2") (pintype "passive"))
      (node (ref "D14") (pin "1") (pinfunction "(C)_1") (pintype "passive"))
      (node (ref "L29") (pin "2") (pinfunction "2_2") (pintype "passive"))
      (node (ref "L32") (pin "1") (pinfunction "1_1") (pintype "passive"))
    )
    (net (code "70") (name "Net-(T2-S3)") (class "Default")
      (node (ref "K4") (pin "5") (pinfunction "5_5") (pintype "passive"))
      (node (ref "K4") (pin "7") (pinfunction "7_7") (pintype "passive"))
      (node (ref "T2") (pin "1") (pinfunction "S3_1") (pintype "passive"))
      (node (ref "T2") (pin "7") (pinfunction "0_7") (pintype "passive"))
    )
    (net (code "71") (name "unconnected-(D4-(C)-Pad1)") (class "Default")
      (node (ref "D4") (pin "1") (pinfunction "(C)_1") (pintype "passive"))
    )
    (net (code "72") (name "unconnected-(K4-Pad4)") (class "Default")
      (node (ref "K4") (pin "4") (pinfunction "4_4") (pintype "passive"))
    )
    (net (code "73") (name "unconnected-(L17-Pad2)") (class "Default")
      (node (ref "L17") (pin "2") (pinfunction "2_2") (pintype "passive"))
    )
    (net (code "74") (name "unconnected-(T1-S2-Pad2)") (class "Default")
      (node (ref "T1") (pin "2") (pinfunction "S2_2") (pintype "passive"))
    )
    (net (code "75") (name "unconnected-(T2-S2-Pad2)") (class "Default")
      (node (ref "T2") (pin "2") (pinfunction "S2_2") (pintype "passive"))
    )
  )
)
